# Indicator.net
KiCad netlist of a schematic drawn in Altium Designer
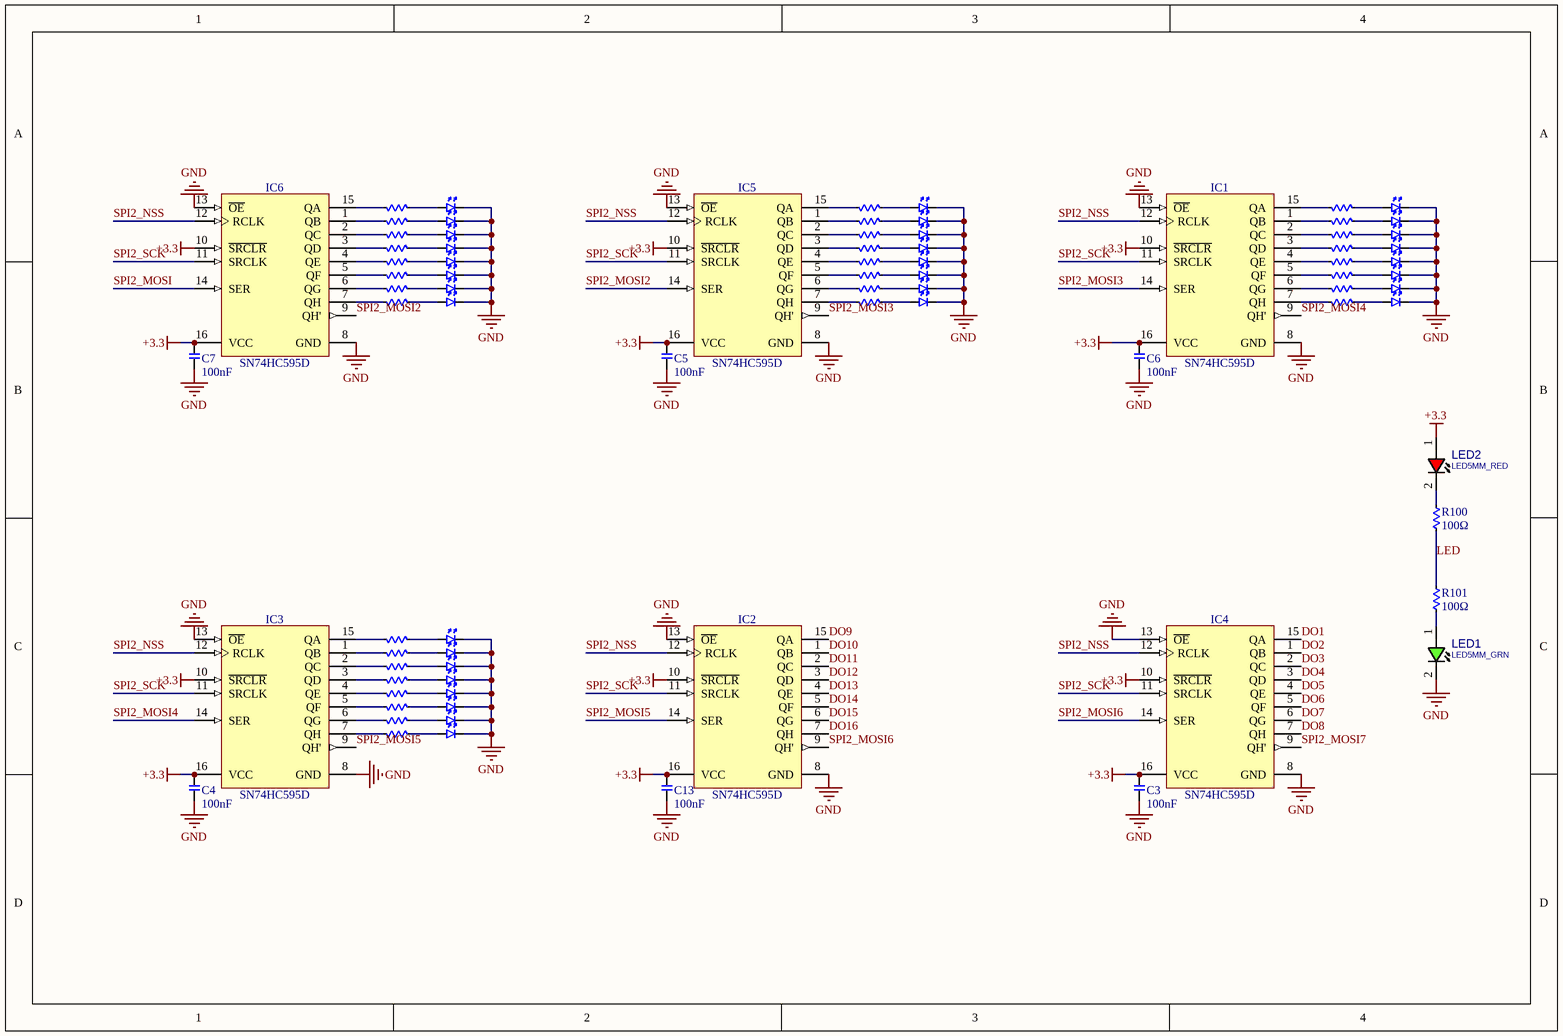
[diagram p0: Indicator.SchDoc]

(export (version "E")
  (design (tool "Eeschema 10.0.6"))
  (components
    (comp (ref "C3") (value "100nF") (footprint "CAP_0603") (libsource (lib "Shahnahad") (part "CAP 100nF")))
    (comp (ref "C4") (value "100nF") (footprint "CAP_0603") (libsource (lib "Shahnahad") (part "CAP 100nF")))
    (comp (ref "C5") (value "100nF") (footprint "CAP_0603") (libsource (lib "Shahnahad") (part "CAP 100nF")))
    (comp (ref "C6") (value "100nF") (footprint "CAP_0603") (libsource (lib "Shahnahad") (part "CAP 100nF")))
    (comp (ref "C7") (value "100nF") (footprint "CAP_0603") (libsource (lib "Shahnahad") (part "CAP 100nF")))
    (comp (ref "C13") (value "100nF") (footprint "CAP_0603") (libsource (lib "Shahnahad") (part "CAP 100nF")))
    (comp (ref "D2") (value "LED") (footprint "LED 0603 GREEN") (libsource (lib "Shahnahad") (part "LED")))
    (comp (ref "D3") (value "LED") (footprint "LED 0603 GREEN") (libsource (lib "Shahnahad") (part "LED")))
    (comp (ref "D4") (value "LED") (footprint "LED 0603 GREEN") (libsource (lib "Shahnahad") (part "LED")))
    (comp (ref "D5") (value "LED") (footprint "LED 0603 GREEN") (libsource (lib "Shahnahad") (part "LED")))
    (comp (ref "D6") (value "LED") (footprint "LED 0603 GREEN") (libsource (lib "Shahnahad") (part "LED")))
    (comp (ref "D7") (value "LED") (footprint "LED 0603 GREEN") (libsource (lib "Shahnahad") (part "LED")))
    (comp (ref "D8") (value "LED") (footprint "LED 0603 GREEN") (libsource (lib "Shahnahad") (part "LED")))
    (comp (ref "D9") (value "LED") (footprint "LED 0603 GREEN") (libsource (lib "Shahnahad") (part "LED")))
    (comp (ref "D10") (value "LED") (footprint "LED 0603 GREEN") (libsource (lib "Shahnahad") (part "LED")))
    (comp (ref "D11") (value "LED") (footprint "LED 0603 GREEN") (libsource (lib "Shahnahad") (part "LED")))
    (comp (ref "D12") (value "LED") (footprint "LED 0603 GREEN") (libsource (lib "Shahnahad") (part "LED")))
    (comp (ref "D13") (value "LED") (footprint "LED 0603 GREEN") (libsource (lib "Shahnahad") (part "LED")))
    (comp (ref "D14") (value "LED") (footprint "LED 0603 GREEN") (libsource (lib "Shahnahad") (part "LED")))
    (comp (ref "D15") (value "LED") (footprint "LED 0603 GREEN") (libsource (lib "Shahnahad") (part "LED")))
    (comp (ref "D16") (value "LED") (footprint "LED 0603 GREEN") (libsource (lib "Shahnahad") (part "LED")))
    (comp (ref "D17") (value "LED") (footprint "LED 0603 GREEN") (libsource (lib "Shahnahad") (part "LED")))
    (comp (ref "D20") (value "LED") (footprint "LED 0603 GREEN") (libsource (lib "Shahnahad") (part "LED")))
    (comp (ref "D21") (value "LED") (footprint "LED 0603 GREEN") (libsource (lib "Shahnahad") (part "LED")))
    (comp (ref "D22") (value "LED") (footprint "LED 0603 GREEN") (libsource (lib "Shahnahad") (part "LED")))
    (comp (ref "D23") (value "LED") (footprint "LED 0603 GREEN") (libsource (lib "Shahnahad") (part "LED")))
    (comp (ref "D24") (value "LED") (footprint "LED 0603 GREEN") (libsource (lib "Shahnahad") (part "LED")))
    (comp (ref "D25") (value "LED") (footprint "LED 0603 GREEN") (libsource (lib "Shahnahad") (part "LED")))
    (comp (ref "D26") (value "LED") (footprint "LED 0603 GREEN") (libsource (lib "Shahnahad") (part "LED")))
    (comp (ref "D27") (value "LED") (footprint "LED 0603 GREEN") (libsource (lib "Shahnahad") (part "LED")))
    (comp (ref "D28") (value "LED") (footprint "LED 0603 GREEN") (libsource (lib "Shahnahad") (part "LED")))
    (comp (ref "D29") (value "LED") (footprint "LED 0603 GREEN") (libsource (lib "Shahnahad") (part "LED")))
    (comp (ref "D30") (value "LED") (footprint "LED 0603 GREEN") (libsource (lib "Shahnahad") (part "LED")))
    (comp (ref "D31") (value "LED") (footprint "LED 0603 GREEN") (libsource (lib "Shahnahad") (part "LED")))
    (comp (ref "D32") (value "LED") (footprint "LED 0603 GREEN") (libsource (lib "Shahnahad") (part "LED")))
    (comp (ref "D33") (value "LED") (footprint "LED 0603 GREEN") (libsource (lib "Shahnahad") (part "LED")))
    (comp (ref "D34") (value "LED") (footprint "LED 0603 GREEN") (libsource (lib "Shahnahad") (part "LED")))
    (comp (ref "D35") (value "LED") (footprint "LED 0603 GREEN") (libsource (lib "Shahnahad") (part "LED")))
    (comp (ref "IC1")
      (value "SN74HC595D")
      (footprint "SOIC127P600X175-16N")
      (description "8-Bit Shift Register With 3-State Output Register")
      (fields (field (name "MANUFACTURER") "TEXAS INSTRUMENTS") (field (name "AUTHOR") "CERN DEM JLC"))
      (libsource (lib "ICs And Semiconductors") (part "74595"))
    )
    (comp (ref "IC2")
      (value "SN74HC595D")
      (footprint "SOIC127P600X175-16N")
      (description "8-Bit Shift Register With 3-State Output Register")
      (fields (field (name "MANUFACTURER") "TEXAS INSTRUMENTS") (field (name "AUTHOR") "CERN DEM JLC"))
      (libsource (lib "ICs And Semiconductors") (part "74595"))
    )
    (comp (ref "IC3")
      (value "SN74HC595D")
      (footprint "SOIC127P600X175-16N")
      (description "8-Bit Shift Register With 3-State Output Register")
      (fields (field (name "MANUFACTURER") "TEXAS INSTRUMENTS") (field (name "AUTHOR") "CERN DEM JLC"))
      (libsource (lib "ICs And Semiconductors") (part "74595"))
    )
    (comp (ref "IC4")
      (value "SN74HC595D")
      (footprint "SOIC127P600X175-16N")
      (description "8-Bit Shift Register With 3-State Output Register")
      (fields (field (name "MANUFACTURER") "TEXAS INSTRUMENTS") (field (name "AUTHOR") "CERN DEM JLC"))
      (libsource (lib "ICs And Semiconductors") (part "74595"))
    )
    (comp (ref "IC5")
      (value "SN74HC595D")
      (footprint "SOIC127P600X175-16N")
      (description "8-Bit Shift Register With 3-State Output Register")
      (fields (field (name "MANUFACTURER") "TEXAS INSTRUMENTS") (field (name "AUTHOR") "CERN DEM JLC"))
      (libsource (lib "ICs And Semiconductors") (part "74595"))
    )
    (comp (ref "IC6")
      (value "SN74HC595D")
      (footprint "SOIC127P600X175-16N")
      (description "8-Bit Shift Register With 3-State Output Register")
      (fields (field (name "MANUFACTURER") "TEXAS INSTRUMENTS") (field (name "AUTHOR") "CERN DEM JLC"))
      (libsource (lib "ICs And Semiconductors") (part "74595"))
    )
    (comp (ref "LED1")
      (value "LED5MM_GRN")
      (footprint "LED5MM_GRN")
      (description "LED, THD, 5MM, GREEN")
      (fields (field (name "MANF") "MANF") (field (name "MANF_P#") "MANF_PART#"))
      (libsource (lib "Chila") (part "LED_THD_5MM_GRN"))
    )
    (comp (ref "LED2")
      (value "LED5MM_RED")
      (footprint "LED5MM_RED")
      (description "LED, THD, 5MM, RED")
      (fields (field (name "MANF") "MANF") (field (name "MANF_P#") "MANF_PART#"))
      (libsource (lib "Chila") (part "LED_THD_5MM_RED"))
    )
    (comp (ref "R20")
      (value "100Ω")
      (footprint "RES ARRAY 4X0603 100")
      (libsource (lib "Shahnahad") (part "RES ARRAY 100"))
    )
    (comp (ref "R21")
      (value "100Ω")
      (footprint "RES ARRAY 4X0603 100")
      (libsource (lib "Shahnahad") (part "RES ARRAY 100"))
    )
    (comp (ref "R22")
      (value "100Ω")
      (footprint "RES ARRAY 4X0603 100")
      (libsource (lib "Shahnahad") (part "RES ARRAY 100"))
    )
    (comp (ref "R23")
      (value "100Ω")
      (footprint "RES ARRAY 4X0603 100")
      (libsource (lib "Shahnahad") (part "RES ARRAY 100"))
    )
    (comp (ref "R25")
      (value "100Ω")
      (footprint "RES ARRAY 4X0603 100")
      (libsource (lib "Shahnahad") (part "RES ARRAY 100"))
    )
    (comp (ref "R26")
      (value "100Ω")
      (footprint "RES ARRAY 4X0603 100")
      (libsource (lib "Shahnahad") (part "RES ARRAY 100"))
    )
    (comp (ref "R27")
      (value "100Ω")
      (footprint "RES ARRAY 4X0603 100")
      (libsource (lib "Shahnahad") (part "RES ARRAY 100"))
    )
    (comp (ref "R28")
      (value "100Ω")
      (footprint "RES ARRAY 4X0603 100")
      (libsource (lib "Shahnahad") (part "RES ARRAY 100"))
    )
    (comp (ref "R100")
      (value "100Ω")
      (footprint "RES 0603 100")
      (libsource (lib "Shahnahad") (part "RES 100"))
    )
    (comp (ref "R101")
      (value "100Ω")
      (footprint "RES 0603 100")
      (libsource (lib "Shahnahad") (part "RES 100"))
    )
  )
  (nets
    (net (code "1") (name "+3.3") (class "Default")
      (node (ref "C13") (pin "1") (pintype "passive"))
      (node (ref "C3") (pin "1") (pintype "passive"))
      (node (ref "C4") (pin "1") (pintype "passive"))
      (node (ref "C5") (pin "1") (pintype "passive"))
      (node (ref "C6") (pin "1") (pintype "passive"))
      (node (ref "C7") (pin "1") (pintype "passive"))
      (node (ref "IC1") (pin "10") (pinfunction "~{SRCLR}_10") (pintype "input"))
      (node (ref "IC1") (pin "16") (pinfunction "VCC_16") (pintype "power_in"))
      (node (ref "IC2") (pin "10") (pinfunction "~{SRCLR}_10") (pintype "input"))
      (node (ref "IC2") (pin "16") (pinfunction "VCC_16") (pintype "power_in"))
      (node (ref "IC3") (pin "10") (pinfunction "~{SRCLR}_10") (pintype "input"))
      (node (ref "IC3") (pin "16") (pinfunction "VCC_16") (pintype "power_in"))
      (node (ref "IC4") (pin "10") (pinfunction "~{SRCLR}_10") (pintype "input"))
      (node (ref "IC4") (pin "16") (pinfunction "VCC_16") (pintype "power_in"))
      (node (ref "IC5") (pin "10") (pinfunction "~{SRCLR}_10") (pintype "input"))
      (node (ref "IC5") (pin "16") (pinfunction "VCC_16") (pintype "power_in"))
      (node (ref "IC6") (pin "10") (pinfunction "~{SRCLR}_10") (pintype "input"))
      (node (ref "IC6") (pin "16") (pinfunction "VCC_16") (pintype "power_in"))
      (node (ref "LED2") (pin "1") (pinfunction "ANODE_1") (pintype "passive"))
    )
    (net (code "2") (name "/DO1") (class "Default")
      (node (ref "IC4") (pin "15") (pinfunction "QA_15") (pintype "tri_state"))
    )
    (net (code "3") (name "/DO2") (class "Default")
      (node (ref "IC4") (pin "1") (pinfunction "QB_1") (pintype "tri_state"))
    )
    (net (code "4") (name "/DO3") (class "Default")
      (node (ref "IC4") (pin "2") (pinfunction "QC_2") (pintype "tri_state"))
    )
    (net (code "5") (name "/DO4") (class "Default")
      (node (ref "IC4") (pin "3") (pinfunction "QD_3") (pintype "tri_state"))
    )
    (net (code "6") (name "/DO5") (class "Default")
      (node (ref "IC4") (pin "4") (pinfunction "QE_4") (pintype "tri_state"))
    )
    (net (code "7") (name "/DO6") (class "Default")
      (node (ref "IC4") (pin "5") (pinfunction "QF_5") (pintype "tri_state"))
    )
    (net (code "8") (name "/DO7") (class "Default")
      (node (ref "IC4") (pin "6") (pinfunction "QG_6") (pintype "tri_state"))
    )
    (net (code "9") (name "/DO8") (class "Default")
      (node (ref "IC4") (pin "7") (pinfunction "QH_7") (pintype "tri_state"))
    )
    (net (code "10") (name "/DO9") (class "Default")
      (node (ref "IC2") (pin "15") (pinfunction "QA_15") (pintype "tri_state"))
    )
    (net (code "11") (name "/DO10") (class "Default")
      (node (ref "IC2") (pin "1") (pinfunction "QB_1") (pintype "tri_state"))
    )
    (net (code "12") (name "/DO11") (class "Default")
      (node (ref "IC2") (pin "2") (pinfunction "QC_2") (pintype "tri_state"))
    )
    (net (code "13") (name "/DO12") (class "Default")
      (node (ref "IC2") (pin "3") (pinfunction "QD_3") (pintype "tri_state"))
    )
    (net (code "14") (name "/DO13") (class "Default")
      (node (ref "IC2") (pin "4") (pinfunction "QE_4") (pintype "tri_state"))
    )
    (net (code "15") (name "/DO14") (class "Default")
      (node (ref "IC2") (pin "5") (pinfunction "QF_5") (pintype "tri_state"))
    )
    (net (code "16") (name "/DO15") (class "Default")
      (node (ref "IC2") (pin "6") (pinfunction "QG_6") (pintype "tri_state"))
    )
    (net (code "17") (name "/DO16") (class "Default")
      (node (ref "IC2") (pin "7") (pinfunction "QH_7") (pintype "tri_state"))
    )
    (net (code "18") (name "/LED") (class "Default")
      (node (ref "R100") (pin "2") (pintype "passive"))
      (node (ref "R101") (pin "1") (pintype "passive"))
    )
    (net (code "19") (name "/SPI2_MOSI") (class "Default")
      (node (ref "IC6") (pin "14") (pinfunction "SER_14") (pintype "input"))
    )
    (net (code "20") (name "/SPI2_MOSI2") (class "Default")
      (node (ref "IC5") (pin "14") (pinfunction "SER_14") (pintype "input"))
      (node (ref "IC6") (pin "9") (pinfunction "QH'_9") (pintype "output"))
    )
    (net (code "21") (name "/SPI2_MOSI3") (class "Default")
      (node (ref "IC1") (pin "14") (pinfunction "SER_14") (pintype "input"))
      (node (ref "IC5") (pin "9") (pinfunction "QH'_9") (pintype "output"))
    )
    (net (code "22") (name "/SPI2_MOSI4") (class "Default")
      (node (ref "IC1") (pin "9") (pinfunction "QH'_9") (pintype "output"))
      (node (ref "IC3") (pin "14") (pinfunction "SER_14") (pintype "input"))
    )
    (net (code "23") (name "/SPI2_MOSI5") (class "Default")
      (node (ref "IC2") (pin "14") (pinfunction "SER_14") (pintype "input"))
      (node (ref "IC3") (pin "9") (pinfunction "QH'_9") (pintype "output"))
    )
    (net (code "24") (name "/SPI2_MOSI6") (class "Default")
      (node (ref "IC2") (pin "9") (pinfunction "QH'_9") (pintype "output"))
      (node (ref "IC4") (pin "14") (pinfunction "SER_14") (pintype "input"))
    )
    (net (code "25") (name "/SPI2_MOSI7") (class "Default")
      (node (ref "IC4") (pin "9") (pinfunction "QH'_9") (pintype "output"))
    )
    (net (code "26") (name "/SPI2_NSS") (class "Default")
      (node (ref "IC1") (pin "12") (pinfunction "RCLK_12") (pintype "input"))
      (node (ref "IC2") (pin "12") (pinfunction "RCLK_12") (pintype "input"))
      (node (ref "IC3") (pin "12") (pinfunction "RCLK_12") (pintype "input"))
      (node (ref "IC4") (pin "12") (pinfunction "RCLK_12") (pintype "input"))
      (node (ref "IC5") (pin "12") (pinfunction "RCLK_12") (pintype "input"))
      (node (ref "IC6") (pin "12") (pinfunction "RCLK_12") (pintype "input"))
    )
    (net (code "27") (name "/SPI2_SCK") (class "Default")
      (node (ref "IC1") (pin "11") (pinfunction "SRCLK_11") (pintype "input"))
      (node (ref "IC2") (pin "11") (pinfunction "SRCLK_11") (pintype "input"))
      (node (ref "IC3") (pin "11") (pinfunction "SRCLK_11") (pintype "input"))
      (node (ref "IC4") (pin "11") (pinfunction "SRCLK_11") (pintype "input"))
      (node (ref "IC5") (pin "11") (pinfunction "SRCLK_11") (pintype "input"))
      (node (ref "IC6") (pin "11") (pinfunction "SRCLK_11") (pintype "input"))
    )
    (net (code "28") (name "GND") (class "Default")
      (node (ref "C13") (pin "2") (pintype "passive"))
      (node (ref "C3") (pin "2") (pintype "passive"))
      (node (ref "C4") (pin "2") (pintype "passive"))
      (node (ref "C5") (pin "2") (pintype "passive"))
      (node (ref "C6") (pin "2") (pintype "passive"))
      (node (ref "C7") (pin "2") (pintype "passive"))
      (node (ref "D10") (pin "2") (pintype "passive"))
      (node (ref "D11") (pin "2") (pintype "passive"))
      (node (ref "D12") (pin "2") (pintype "passive"))
      (node (ref "D13") (pin "2") (pintype "passive"))
      (node (ref "D14") (pin "2") (pintype "passive"))
      (node (ref "D15") (pin "2") (pintype "passive"))
      (node (ref "D16") (pin "2") (pintype "passive"))
      (node (ref "D17") (pin "2") (pintype "passive"))
      (node (ref "D2") (pin "2") (pintype "passive"))
      (node (ref "D20") (pin "2") (pintype "passive"))
      (node (ref "D21") (pin "2") (pintype "passive"))
      (node (ref "D22") (pin "2") (pintype "passive"))
      (node (ref "D23") (pin "2") (pintype "passive"))
      (node (ref "D24") (pin "2") (pintype "passive"))
      (node (ref "D25") (pin "2") (pintype "passive"))
      (node (ref "D26") (pin "2") (pintype "passive"))
      (node (ref "D27") (pin "2") (pintype "passive"))
      (node (ref "D28") (pin "2") (pintype "passive"))
      (node (ref "D29") (pin "2") (pintype "passive"))
      (node (ref "D3") (pin "2") (pintype "passive"))
      (node (ref "D30") (pin "2") (pintype "passive"))
      (node (ref "D31") (pin "2") (pintype "passive"))
      (node (ref "D32") (pin "2") (pintype "passive"))
      (node (ref "D33") (pin "2") (pintype "passive"))
      (node (ref "D34") (pin "2") (pintype "passive"))
      (node (ref "D35") (pin "2") (pintype "passive"))
      (node (ref "D4") (pin "2") (pintype "passive"))
      (node (ref "D5") (pin "2") (pintype "passive"))
      (node (ref "D6") (pin "2") (pintype "passive"))
      (node (ref "D7") (pin "2") (pintype "passive"))
      (node (ref "D8") (pin "2") (pintype "passive"))
      (node (ref "D9") (pin "2") (pintype "passive"))
      (node (ref "IC1") (pin "13") (pinfunction "~{OE}_13") (pintype "input"))
      (node (ref "IC1") (pin "8") (pinfunction "GND_8") (pintype "power_in"))
      (node (ref "IC2") (pin "13") (pinfunction "~{OE}_13") (pintype "input"))
      (node (ref "IC2") (pin "8") (pinfunction "GND_8") (pintype "power_in"))
      (node (ref "IC3") (pin "13") (pinfunction "~{OE}_13") (pintype "input"))
      (node (ref "IC3") (pin "8") (pinfunction "GND_8") (pintype "power_in"))
      (node (ref "IC4") (pin "13") (pinfunction "~{OE}_13") (pintype "input"))
      (node (ref "IC4") (pin "8") (pinfunction "GND_8") (pintype "power_in"))
      (node (ref "IC5") (pin "13") (pinfunction "~{OE}_13") (pintype "input"))
      (node (ref "IC5") (pin "8") (pinfunction "GND_8") (pintype "power_in"))
      (node (ref "IC6") (pin "13") (pinfunction "~{OE}_13") (pintype "input"))
      (node (ref "IC6") (pin "8") (pinfunction "GND_8") (pintype "power_in"))
      (node (ref "LED1") (pin "2") (pinfunction "CATHODE_2") (pintype "passive"))
    )
    (net (code "29") (name "Net-(D2-Pad1)") (class "Default")
      (node (ref "D2") (pin "1") (pintype "passive"))
      (node (ref "R20") (pin "4") (pintype "passive"))
    )
    (net (code "30") (name "Net-(D3-Pad1)") (class "Default")
      (node (ref "D3") (pin "1") (pintype "passive"))
      (node (ref "R20") (pin "3") (pintype "passive"))
    )
    (net (code "31") (name "Net-(D4-Pad1)") (class "Default")
      (node (ref "D4") (pin "1") (pintype "passive"))
      (node (ref "R20") (pin "2") (pintype "passive"))
    )
    (net (code "32") (name "Net-(D5-Pad1)") (class "Default")
      (node (ref "D5") (pin "1") (pintype "passive"))
      (node (ref "R20") (pin "1") (pintype "passive"))
    )
    (net (code "33") (name "Net-(D6-Pad1)") (class "Default")
      (node (ref "D6") (pin "1") (pintype "passive"))
      (node (ref "R21") (pin "4") (pintype "passive"))
    )
    (net (code "34") (name "Net-(D7-Pad1)") (class "Default")
      (node (ref "D7") (pin "1") (pintype "passive"))
      (node (ref "R21") (pin "3") (pintype "passive"))
    )
    (net (code "35") (name "Net-(D8-Pad1)") (class "Default")
      (node (ref "D8") (pin "1") (pintype "passive"))
      (node (ref "R21") (pin "2") (pintype "passive"))
    )
    (net (code "36") (name "Net-(D9-Pad1)") (class "Default")
      (node (ref "D9") (pin "1") (pintype "passive"))
      (node (ref "R21") (pin "1") (pintype "passive"))
    )
    (net (code "37") (name "Net-(D10-Pad1)") (class "Default")
      (node (ref "D10") (pin "1") (pintype "passive"))
      (node (ref "R22") (pin "4") (pintype "passive"))
    )
    (net (code "38") (name "Net-(D11-Pad1)") (class "Default")
      (node (ref "D11") (pin "1") (pintype "passive"))
      (node (ref "R22") (pin "3") (pintype "passive"))
    )
    (net (code "39") (name "Net-(D12-Pad1)") (class "Default")
      (node (ref "D12") (pin "1") (pintype "passive"))
      (node (ref "R22") (pin "2") (pintype "passive"))
    )
    (net (code "40") (name "Net-(D13-Pad1)") (class "Default")
      (node (ref "D13") (pin "1") (pintype "passive"))
      (node (ref "R22") (pin "1") (pintype "passive"))
    )
    (net (code "41") (name "Net-(D14-Pad1)") (class "Default")
      (node (ref "D14") (pin "1") (pintype "passive"))
      (node (ref "R23") (pin "4") (pintype "passive"))
    )
    (net (code "42") (name "Net-(D15-Pad1)") (class "Default")
      (node (ref "D15") (pin "1") (pintype "passive"))
      (node (ref "R23") (pin "3") (pintype "passive"))
    )
    (net (code "43") (name "Net-(D16-Pad1)") (class "Default")
      (node (ref "D16") (pin "1") (pintype "passive"))
      (node (ref "R23") (pin "2") (pintype "passive"))
    )
    (net (code "44") (name "Net-(D17-Pad1)") (class "Default")
      (node (ref "D17") (pin "1") (pintype "passive"))
      (node (ref "R23") (pin "1") (pintype "passive"))
    )
    (net (code "45") (name "Net-(D20-Pad1)") (class "Default")
      (node (ref "D20") (pin "1") (pintype "passive"))
      (node (ref "R25") (pin "1") (pintype "passive"))
    )
    (net (code "46") (name "Net-(D21-Pad1)") (class "Default")
      (node (ref "D21") (pin "1") (pintype "passive"))
      (node (ref "R25") (pin "2") (pintype "passive"))
    )
    (net (code "47") (name "Net-(D22-Pad1)") (class "Default")
      (node (ref "D22") (pin "1") (pintype "passive"))
      (node (ref "R25") (pin "3") (pintype "passive"))
    )
    (net (code "48") (name "Net-(D23-Pad1)") (class "Default")
      (node (ref "D23") (pin "1") (pintype "passive"))
      (node (ref "R25") (pin "4") (pintype "passive"))
    )
    (net (code "49") (name "Net-(D24-Pad1)") (class "Default")
      (node (ref "D24") (pin "1") (pintype "passive"))
      (node (ref "R26") (pin "1") (pintype "passive"))
    )
    (net (code "50") (name "Net-(D25-Pad1)") (class "Default")
      (node (ref "D25") (pin "1") (pintype "passive"))
      (node (ref "R26") (pin "2") (pintype "passive"))
    )
    (net (code "51") (name "Net-(D26-Pad1)") (class "Default")
      (node (ref "D26") (pin "1") (pintype "passive"))
      (node (ref "R26") (pin "3") (pintype "passive"))
    )
    (net (code "52") (name "Net-(D27-Pad1)") (class "Default")
      (node (ref "D27") (pin "1") (pintype "passive"))
      (node (ref "R26") (pin "4") (pintype "passive"))
    )
    (net (code "53") (name "Net-(D28-Pad1)") (class "Default")
      (node (ref "D28") (pin "1") (pintype "passive"))
      (node (ref "R27") (pin "1") (pintype "passive"))
    )
    (net (code "54") (name "Net-(D29-Pad1)") (class "Default")
      (node (ref "D29") (pin "1") (pintype "passive"))
      (node (ref "R27") (pin "2") (pintype "passive"))
    )
    (net (code "55") (name "Net-(D30-Pad1)") (class "Default")
      (node (ref "D30") (pin "1") (pintype "passive"))
      (node (ref "R27") (pin "3") (pintype "passive"))
    )
    (net (code "56") (name "Net-(D31-Pad1)") (class "Default")
      (node (ref "D31") (pin "1") (pintype "passive"))
      (node (ref "R27") (pin "4") (pintype "passive"))
    )
    (net (code "57") (name "Net-(D32-Pad1)") (class "Default")
      (node (ref "D32") (pin "1") (pintype "passive"))
      (node (ref "R28") (pin "1") (pintype "passive"))
    )
    (net (code "58") (name "Net-(D33-Pad1)") (class "Default")
      (node (ref "D33") (pin "1") (pintype "passive"))
      (node (ref "R28") (pin "2") (pintype "passive"))
    )
    (net (code "59") (name "Net-(D34-Pad1)") (class "Default")
      (node (ref "D34") (pin "1") (pintype "passive"))
      (node (ref "R28") (pin "3") (pintype "passive"))
    )
    (net (code "60") (name "Net-(D35-Pad1)") (class "Default")
      (node (ref "D35") (pin "1") (pintype "passive"))
      (node (ref "R28") (pin "4") (pintype "passive"))
    )
    (net (code "61") (name "Net-(IC1-QA)") (class "Default")
      (node (ref "IC1") (pin "15") (pinfunction "QA_15") (pintype "tri_state"))
      (node (ref "R21") (pin "8") (pintype "passive"))
    )
    (net (code "62") (name "Net-(IC1-QB)") (class "Default")
      (node (ref "IC1") (pin "1") (pinfunction "QB_1") (pintype "tri_state"))
      (node (ref "R21") (pin "7") (pintype "passive"))
    )
    (net (code "63") (name "Net-(IC1-QC)") (class "Default")
      (node (ref "IC1") (pin "2") (pinfunction "QC_2") (pintype "tri_state"))
      (node (ref "R21") (pin "6") (pintype "passive"))
    )
    (net (code "64") (name "Net-(IC1-QD)") (class "Default")
      (node (ref "IC1") (pin "3") (pinfunction "QD_3") (pintype "tri_state"))
      (node (ref "R21") (pin "5") (pintype "passive"))
    )
    (net (code "65") (name "Net-(IC1-QE)") (class "Default")
      (node (ref "IC1") (pin "4") (pinfunction "QE_4") (pintype "tri_state"))
      (node (ref "R20") (pin "8") (pintype "passive"))
    )
    (net (code "66") (name "Net-(IC1-QF)") (class "Default")
      (node (ref "IC1") (pin "5") (pinfunction "QF_5") (pintype "tri_state"))
      (node (ref "R20") (pin "7") (pintype "passive"))
    )
    (net (code "67") (name "Net-(IC1-QG)") (class "Default")
      (node (ref "IC1") (pin "6") (pinfunction "QG_6") (pintype "tri_state"))
      (node (ref "R20") (pin "6") (pintype "passive"))
    )
    (net (code "68") (name "Net-(IC1-QH)") (class "Default")
      (node (ref "IC1") (pin "7") (pinfunction "QH_7") (pintype "tri_state"))
      (node (ref "R20") (pin "5") (pintype "passive"))
    )
    (net (code "69") (name "Net-(IC3-QA)") (class "Default")
      (node (ref "IC3") (pin "15") (pinfunction "QA_15") (pintype "tri_state"))
      (node (ref "R23") (pin "8") (pintype "passive"))
    )
    (net (code "70") (name "Net-(IC3-QB)") (class "Default")
      (node (ref "IC3") (pin "1") (pinfunction "QB_1") (pintype "tri_state"))
      (node (ref "R23") (pin "7") (pintype "passive"))
    )
    (net (code "71") (name "Net-(IC3-QC)") (class "Default")
      (node (ref "IC3") (pin "2") (pinfunction "QC_2") (pintype "tri_state"))
      (node (ref "R23") (pin "6") (pintype "passive"))
    )
    (net (code "72") (name "Net-(IC3-QD)") (class "Default")
      (node (ref "IC3") (pin "3") (pinfunction "QD_3") (pintype "tri_state"))
      (node (ref "R23") (pin "5") (pintype "passive"))
    )
    (net (code "73") (name "Net-(IC3-QE)") (class "Default")
      (node (ref "IC3") (pin "4") (pinfunction "QE_4") (pintype "tri_state"))
      (node (ref "R22") (pin "8") (pintype "passive"))
    )
    (net (code "74") (name "Net-(IC3-QF)") (class "Default")
      (node (ref "IC3") (pin "5") (pinfunction "QF_5") (pintype "tri_state"))
      (node (ref "R22") (pin "7") (pintype "passive"))
    )
    (net (code "75") (name "Net-(IC3-QG)") (class "Default")
      (node (ref "IC3") (pin "6") (pinfunction "QG_6") (pintype "tri_state"))
      (node (ref "R22") (pin "6") (pintype "passive"))
    )
    (net (code "76") (name "Net-(IC3-QH)") (class "Default")
      (node (ref "IC3") (pin "7") (pinfunction "QH_7") (pintype "tri_state"))
      (node (ref "R22") (pin "5") (pintype "passive"))
    )
    (net (code "77") (name "Net-(IC5-QA)") (class "Default")
      (node (ref "IC5") (pin "15") (pinfunction "QA_15") (pintype "tri_state"))
      (node (ref "R25") (pin "8") (pintype "passive"))
    )
    (net (code "78") (name "Net-(IC5-QB)") (class "Default")
      (node (ref "IC5") (pin "1") (pinfunction "QB_1") (pintype "tri_state"))
      (node (ref "R25") (pin "7") (pintype "passive"))
    )
    (net (code "79") (name "Net-(IC5-QC)") (class "Default")
      (node (ref "IC5") (pin "2") (pinfunction "QC_2") (pintype "tri_state"))
      (node (ref "R25") (pin "6") (pintype "passive"))
    )
    (net (code "80") (name "Net-(IC5-QD)") (class "Default")
      (node (ref "IC5") (pin "3") (pinfunction "QD_3") (pintype "tri_state"))
      (node (ref "R25") (pin "5") (pintype "passive"))
    )
    (net (code "81") (name "Net-(IC5-QE)") (class "Default")
      (node (ref "IC5") (pin "4") (pinfunction "QE_4") (pintype "tri_state"))
      (node (ref "R26") (pin "8") (pintype "passive"))
    )
    (net (code "82") (name "Net-(IC5-QF)") (class "Default")
      (node (ref "IC5") (pin "5") (pinfunction "QF_5") (pintype "tri_state"))
      (node (ref "R26") (pin "7") (pintype "passive"))
    )
    (net (code "83") (name "Net-(IC5-QG)") (class "Default")
      (node (ref "IC5") (pin "6") (pinfunction "QG_6") (pintype "tri_state"))
      (node (ref "R26") (pin "6") (pintype "passive"))
    )
    (net (code "84") (name "Net-(IC5-QH)") (class "Default")
      (node (ref "IC5") (pin "7") (pinfunction "QH_7") (pintype "tri_state"))
      (node (ref "R26") (pin "5") (pintype "passive"))
    )
    (net (code "85") (name "Net-(IC6-QA)") (class "Default")
      (node (ref "IC6") (pin "15") (pinfunction "QA_15") (pintype "tri_state"))
      (node (ref "R27") (pin "8") (pintype "passive"))
    )
    (net (code "86") (name "Net-(IC6-QB)") (class "Default")
      (node (ref "IC6") (pin "1") (pinfunction "QB_1") (pintype "tri_state"))
      (node (ref "R27") (pin "7") (pintype "passive"))
    )
    (net (code "87") (name "Net-(IC6-QC)") (class "Default")
      (node (ref "IC6") (pin "2") (pinfunction "QC_2") (pintype "tri_state"))
      (node (ref "R27") (pin "6") (pintype "passive"))
    )
    (net (code "88") (name "Net-(IC6-QD)") (class "Default")
      (node (ref "IC6") (pin "3") (pinfunction "QD_3") (pintype "tri_state"))
      (node (ref "R27") (pin "5") (pintype "passive"))
    )
    (net (code "89") (name "Net-(IC6-QE)") (class "Default")
      (node (ref "IC6") (pin "4") (pinfunction "QE_4") (pintype "tri_state"))
      (node (ref "R28") (pin "8") (pintype "passive"))
    )
    (net (code "90") (name "Net-(IC6-QF)") (class "Default")
      (node (ref "IC6") (pin "5") (pinfunction "QF_5") (pintype "tri_state"))
      (node (ref "R28") (pin "7") (pintype "passive"))
    )
    (net (code "91") (name "Net-(IC6-QG)") (class "Default")
      (node (ref "IC6") (pin "6") (pinfunction "QG_6") (pintype "tri_state"))
      (node (ref "R28") (pin "6") (pintype "passive"))
    )
    (net (code "92") (name "Net-(IC6-QH)") (class "Default")
      (node (ref "IC6") (pin "7") (pinfunction "QH_7") (pintype "tri_state"))
      (node (ref "R28") (pin "5") (pintype "passive"))
    )
    (net (code "93") (name "Net-(LED1-ANODE)") (class "Default")
      (node (ref "LED1") (pin "1") (pinfunction "ANODE_1") (pintype "passive"))
      (node (ref "R101") (pin "2") (pintype "passive"))
    )
    (net (code "94") (name "Net-(LED2-CATHODE)") (class "Default")
      (node (ref "LED2") (pin "2") (pinfunction "CATHODE_2") (pintype "passive"))
      (node (ref "R100") (pin "1") (pintype "passive"))
    )
  )
)
